# HB-UNI-Sen-RFID-RC.net
KiCad netlist of a schematic drawn in EAGLE
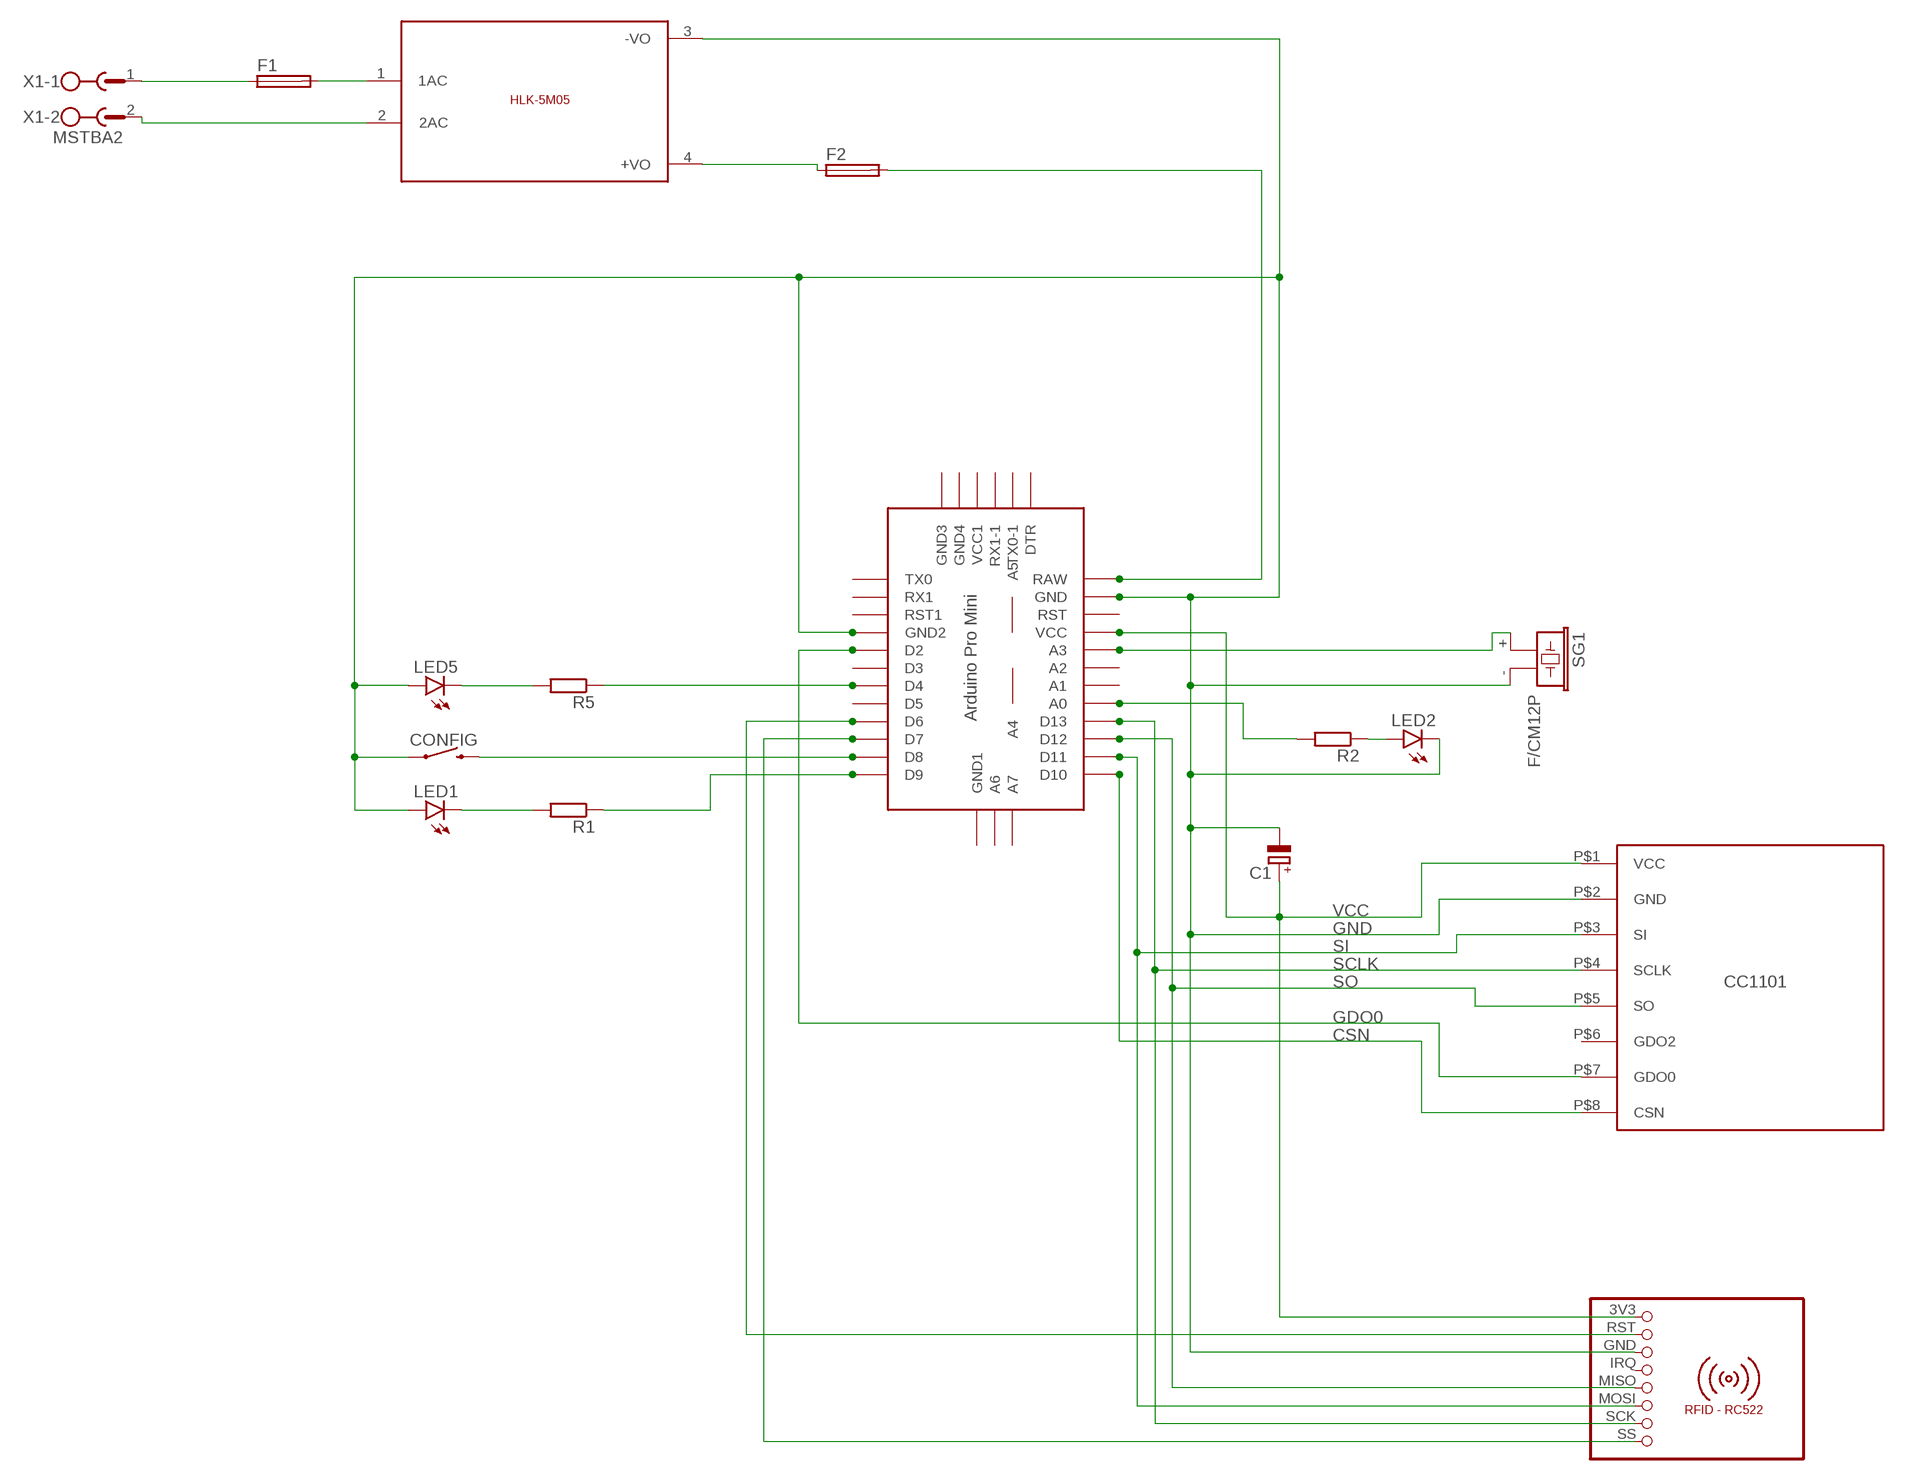
[diagram p0: schematic, sheet 1]

(export (version "E")
  (design (tool "Eeschema 10.0.6"))
  (components
    (comp (ref "C1")
      (value "CPOL-EUE2.5-5")
      (footprint "eagle-import:E2,5-5")
      (libsource (lib "eagle-import") (part "CPOL-EUE2.5-5"))
    )
    (comp (ref "CONFIG")
      (value "MOMENTARY-SWITCH-SPST-PTH-6.0MM-KIT")
      (footprint "eagle-import:TACTILE_SWITCH_PTH_6.0MM_KIT")
      (libsource (lib "eagle-import") (part "MOMENTARY-SWITCH-SPST-PTH-6.0MM-KIT"))
    )
    (comp (ref "F1")
      (value "SH22,5A")
      (footprint "eagle-import:SH22,5A")
      (fields (field (name "MPN") "0031.7701.11"))
      (libsource (lib "eagle-import") (part "SH22,5A"))
    )
    (comp (ref "F2")
      (value "SH22,5A")
      (footprint "eagle-import:SH22,5A")
      (fields (field (name "MPN") "0031.7701.11"))
      (libsource (lib "eagle-import") (part "SH22,5A"))
    )
    (comp (ref "LED1")
      (value "LED3MM")
      (footprint "eagle-import:LED3MM")
      (libsource (lib "eagle-import") (part "LED3MM"))
    )
    (comp (ref "LED2")
      (value "LED3MM")
      (footprint "eagle-import:LED3MM")
      (libsource (lib "eagle-import") (part "LED3MM"))
    )
    (comp (ref "LED5")
      (value "LED3MM")
      (footprint "eagle-import:LED3MM")
      (libsource (lib "eagle-import") (part "LED3MM"))
    )
    (comp (ref "M1")
      (value "RFID-RC522")
      (footprint "eagle-import:RFID-RC522")
      (libsource (lib "eagle-import") (part "RFID-RC522"))
    )
    (comp (ref "R1")
      (value "R-EU_0309/10")
      (footprint "eagle-import:0309_10")
      (libsource (lib "eagle-import") (part "R-EU_0309/10"))
    )
    (comp (ref "R2")
      (value "R-EU_0309/10")
      (footprint "eagle-import:0309_10")
      (libsource (lib "eagle-import") (part "R-EU_0309/10"))
    )
    (comp (ref "R5")
      (value "R-EU_0309/10")
      (footprint "eagle-import:0309_10")
      (libsource (lib "eagle-import") (part "R-EU_0309/10"))
    )
    (comp (ref "SG1")
      (value "F/CM12P")
      (footprint "eagle-import:F_CM12P")
      (libsource (lib "eagle-import") (part "F/CM12P"))
    )
    (comp (ref "U$1")
      (value "CC1101")
      (footprint "eagle-import:CC1101")
      (libsource (lib "eagle-import") (part "CC1101"))
    )
    (comp (ref "U$2")
      (value "ABK-PRO-MINI")
      (footprint "eagle-import:ABK-PRO-MINI")
      (libsource (lib "eagle-import") (part "ABK-PRO-MINI"))
    )
    (comp (ref "U$3")
      (value "5VDC/5W")
      (footprint "eagle-import:HLK-5M05")
      (libsource (lib "eagle-import") (part "HLK-5M05"))
    )
    (comp (ref "X1")
      (value "MSTBA2")
      (footprint "eagle-import:MSTBA2")
      (fields (field (name "MF") "FARNELL") (field (name "MPN") "1757242"))
      (libsource (lib "eagle-import") (part "MSTBA2"))
    )
  )
  (nets
    (net (code "1") (name "/CSN") (class "Default")
      (node (ref "U$1") (pin "P$8") (pinfunction "CSN_P$8") (pintype "bidirectional"))
      (node (ref "U$2") (pin "D10") (pinfunction "D10_D10") (pintype "bidirectional"))
    )
    (net (code "2") (name "/GDO0") (class "Default")
      (node (ref "U$1") (pin "P$7") (pinfunction "GDO0_P$7") (pintype "bidirectional"))
      (node (ref "U$2") (pin "D2") (pinfunction "D2_D2") (pintype "bidirectional"))
    )
    (net (code "3") (name "/GND") (class "Default")
      (node (ref "C1") (pin "-") (pinfunction "-_-") (pintype "passive"))
      (node (ref "CONFIG") (pin "1") (pinfunction "1_1") (pintype "passive"))
      (node (ref "LED1") (pin "A") (pinfunction "A_A") (pintype "passive"))
      (node (ref "LED2") (pin "K") (pinfunction "C_K") (pintype "passive"))
      (node (ref "LED5") (pin "A") (pinfunction "A_A") (pintype "passive"))
      (node (ref "M1") (pin "GND") (pinfunction "3_GND") (pintype "passive"))
      (node (ref "SG1") (pin "-") (pinfunction "2_-") (pintype "passive"))
      (node (ref "U$1") (pin "P$2") (pinfunction "GND_P$2") (pintype "bidirectional"))
      (node (ref "U$2") (pin "GND") (pinfunction "GND_GND") (pintype "bidirectional"))
      (node (ref "U$2") (pin "GND1") (pinfunction "GND2_GND1") (pintype "bidirectional"))
      (node (ref "U$3") (pin "3") (pinfunction "-VO_3") (pintype "bidirectional"))
    )
    (net (code "4") (name "/SCLK") (class "Default")
      (node (ref "M1") (pin "SCK") (pinfunction "7_SCK") (pintype "passive"))
      (node (ref "U$1") (pin "P$4") (pinfunction "SCLK_P$4") (pintype "bidirectional"))
      (node (ref "U$2") (pin "D13") (pinfunction "D13_D13") (pintype "bidirectional"))
    )
    (net (code "5") (name "/SI") (class "Default")
      (node (ref "M1") (pin "MOSI") (pinfunction "6_MOSI") (pintype "passive"))
      (node (ref "U$1") (pin "P$3") (pinfunction "SI_P$3") (pintype "bidirectional"))
      (node (ref "U$2") (pin "D11") (pinfunction "D11_D11") (pintype "bidirectional"))
    )
    (net (code "6") (name "/SO") (class "Default")
      (node (ref "M1") (pin "MISO") (pinfunction "5_MISO") (pintype "passive"))
      (node (ref "U$1") (pin "P$5") (pinfunction "SO_P$5") (pintype "bidirectional"))
      (node (ref "U$2") (pin "D12") (pinfunction "D12_D12") (pintype "bidirectional"))
    )
    (net (code "7") (name "/VCC") (class "Default")
      (node (ref "C1") (pin "+") (pinfunction "+_+") (pintype "passive"))
      (node (ref "M1") (pin "3V3") (pinfunction "1_3V3") (pintype "passive"))
      (node (ref "U$1") (pin "P$1") (pinfunction "VCC_P$1") (pintype "bidirectional"))
      (node (ref "U$2") (pin "VCC") (pinfunction "VCC_VCC") (pintype "bidirectional"))
    )
    (net (code "8") (name "Net-(CONFIG-2)") (class "Default")
      (node (ref "CONFIG") (pin "3") (pinfunction "2_3") (pintype "passive"))
      (node (ref "U$2") (pin "D8") (pinfunction "D8_D8") (pintype "bidirectional"))
    )
    (net (code "9") (name "Net-(F1-Pad1)") (class "Default")
      (node (ref "F1") (pin "1") (pinfunction "1_1") (pintype "passive"))
      (node (ref "X1") (pin "1") (pinfunction "1_1") (pintype "passive"))
    )
    (net (code "10") (name "Net-(F2-Pad2)") (class "Default")
      (node (ref "F2") (pin "2") (pinfunction "2_2") (pintype "passive"))
      (node (ref "U$2") (pin "RAW") (pinfunction "RAW_RAW") (pintype "bidirectional"))
    )
    (net (code "11") (name "Net-(LED1-C)") (class "Default")
      (node (ref "LED1") (pin "K") (pinfunction "C_K") (pintype "passive"))
      (node (ref "R1") (pin "2") (pinfunction "2_2") (pintype "passive"))
    )
    (net (code "12") (name "Net-(LED2-PadA)") (class "Default")
      (node (ref "LED2") (pin "A") (pinfunction "A_A") (pintype "passive"))
      (node (ref "R2") (pin "1") (pinfunction "1_1") (pintype "passive"))
    )
    (net (code "13") (name "Net-(LED5-C)") (class "Default")
      (node (ref "LED5") (pin "K") (pinfunction "C_K") (pintype "passive"))
      (node (ref "R5") (pin "2") (pinfunction "2_2") (pintype "passive"))
    )
    (net (code "14") (name "Net-(M1-2)") (class "Default")
      (node (ref "M1") (pin "RST") (pinfunction "2_RST") (pintype "passive"))
      (node (ref "U$2") (pin "D6") (pinfunction "D6_D6") (pintype "bidirectional"))
    )
    (net (code "15") (name "Net-(M1-8)") (class "Default")
      (node (ref "M1") (pin "SS") (pinfunction "8_SS") (pintype "passive"))
      (node (ref "U$2") (pin "D7") (pinfunction "D7_D7") (pintype "bidirectional"))
    )
    (net (code "16") (name "Net-(R1-Pad1)") (class "Default")
      (node (ref "R1") (pin "1") (pinfunction "1_1") (pintype "passive"))
      (node (ref "U$2") (pin "D9") (pinfunction "D9_D9") (pintype "bidirectional"))
    )
    (net (code "17") (name "Net-(R2-Pad2)") (class "Default")
      (node (ref "R2") (pin "2") (pinfunction "2_2") (pintype "passive"))
      (node (ref "U$2") (pin "A0") (pinfunction "A0_A0") (pintype "bidirectional"))
    )
    (net (code "18") (name "Net-(R5-Pad1)") (class "Default")
      (node (ref "R5") (pin "1") (pinfunction "1_1") (pintype "passive"))
      (node (ref "U$2") (pin "D4") (pinfunction "D4_D4") (pintype "bidirectional"))
    )
    (net (code "19") (name "Net-(SG1-1)") (class "Default")
      (node (ref "SG1") (pin "+") (pinfunction "1_+") (pintype "passive"))
      (node (ref "U$2") (pin "A3") (pinfunction "A3_A3") (pintype "bidirectional"))
    )
    (net (code "20") (name "Net-(U$3-+VO)") (class "Default")
      (node (ref "F2") (pin "1") (pinfunction "1_1") (pintype "passive"))
      (node (ref "U$3") (pin "4") (pinfunction "+VO_4") (pintype "bidirectional"))
    )
    (net (code "21") (name "Net-(U$3-1AC)") (class "Default")
      (node (ref "F1") (pin "2") (pinfunction "2_2") (pintype "passive"))
      (node (ref "U$3") (pin "1") (pinfunction "1AC_1") (pintype "bidirectional"))
    )
    (net (code "22") (name "Net-(U$3-2AC)") (class "Default")
      (node (ref "U$3") (pin "2") (pinfunction "2AC_2") (pintype "bidirectional"))
      (node (ref "X1") (pin "2") (pinfunction "1_2") (pintype "passive"))
    )
    (net (code "23") (name "unconnected-(M1-4-PadIRQ)") (class "Default")
      (node (ref "M1") (pin "IRQ") (pinfunction "4_IRQ") (pintype "passive"))
    )
    (net (code "24") (name "unconnected-(U$1-GDO2-PadP$6)") (class "Default")
      (node (ref "U$1") (pin "P$6") (pinfunction "GDO2_P$6") (pintype "bidirectional"))
    )
    (net (code "25") (name "unconnected-(U$2-GND1-PadGND4)") (class "Default")
      (node (ref "U$2") (pin "GND4") (pinfunction "GND1_GND4") (pintype "bidirectional"))
    )
    (net (code "26") (name "unconnected-(U$2-GND3-PadGND2)") (class "Default")
      (node (ref "U$2") (pin "GND2") (pinfunction "GND3_GND2") (pintype "bidirectional"))
    )
    (net (code "27") (name "unconnected-(U$2-GND4-PadGND3)") (class "Default")
      (node (ref "U$2") (pin "GND3") (pinfunction "GND4_GND3") (pintype "bidirectional"))
    )
    (net (code "28") (name "unconnected-(U$2-PadA1)") (class "Default")
      (node (ref "U$2") (pin "A1") (pinfunction "A1_A1") (pintype "bidirectional"))
    )
    (net (code "29") (name "unconnected-(U$2-PadA2)") (class "Default")
      (node (ref "U$2") (pin "A2") (pinfunction "A2_A2") (pintype "bidirectional"))
    )
    (net (code "30") (name "unconnected-(U$2-PadA4)") (class "Default")
      (node (ref "U$2") (pin "A4") (pinfunction "A4_A4") (pintype "bidirectional"))
    )
    (net (code "31") (name "unconnected-(U$2-PadA5)") (class "Default")
      (node (ref "U$2") (pin "A5") (pinfunction "A5_A5") (pintype "bidirectional"))
    )
    (net (code "32") (name "unconnected-(U$2-PadA6)") (class "Default")
      (node (ref "U$2") (pin "A6") (pinfunction "A6_A6") (pintype "bidirectional"))
    )
    (net (code "33") (name "unconnected-(U$2-PadA7)") (class "Default")
      (node (ref "U$2") (pin "A7") (pinfunction "A7_A7") (pintype "bidirectional"))
    )
    (net (code "34") (name "unconnected-(U$2-PadD3)") (class "Default")
      (node (ref "U$2") (pin "D3") (pinfunction "D3_D3") (pintype "bidirectional"))
    )
    (net (code "35") (name "unconnected-(U$2-PadD5)") (class "Default")
      (node (ref "U$2") (pin "D5") (pinfunction "D5_D5") (pintype "bidirectional"))
    )
    (net (code "36") (name "unconnected-(U$2-PadDTR)") (class "Default")
      (node (ref "U$2") (pin "DTR") (pinfunction "DTR_DTR") (pintype "bidirectional"))
    )
    (net (code "37") (name "unconnected-(U$2-PadRST)") (class "Default")
      (node (ref "U$2") (pin "RST") (pinfunction "RST_RST") (pintype "bidirectional"))
    )
    (net (code "38") (name "unconnected-(U$2-PadRST1)") (class "Default")
      (node (ref "U$2") (pin "RST1") (pinfunction "RST1_RST1") (pintype "bidirectional"))
    )
    (net (code "39") (name "unconnected-(U$2-PadRX1)") (class "Default")
      (node (ref "U$2") (pin "RX1") (pinfunction "RX1_RX1") (pintype "bidirectional"))
    )
    (net (code "40") (name "unconnected-(U$2-PadRX1-1)") (class "Default")
      (node (ref "U$2") (pin "RX1-1") (pinfunction "RX1-1_RX1-1") (pintype "bidirectional"))
    )
    (net (code "41") (name "unconnected-(U$2-PadTX0)") (class "Default")
      (node (ref "U$2") (pin "TX0") (pinfunction "TX0_TX0") (pintype "bidirectional"))
    )
    (net (code "42") (name "unconnected-(U$2-PadTX0-1)") (class "Default")
      (node (ref "U$2") (pin "TX0-1") (pinfunction "TX0-1_TX0-1") (pintype "bidirectional"))
    )
    (net (code "43") (name "unconnected-(U$2-PadVCC1)") (class "Default")
      (node (ref "U$2") (pin "VCC1") (pinfunction "VCC1_VCC1") (pintype "bidirectional"))
    )
  )
)
